# Ada_-_Base_Block_-_PSU_and_Connectors_Is.net
KiCad netlist of a schematic drawn in Altium Designer
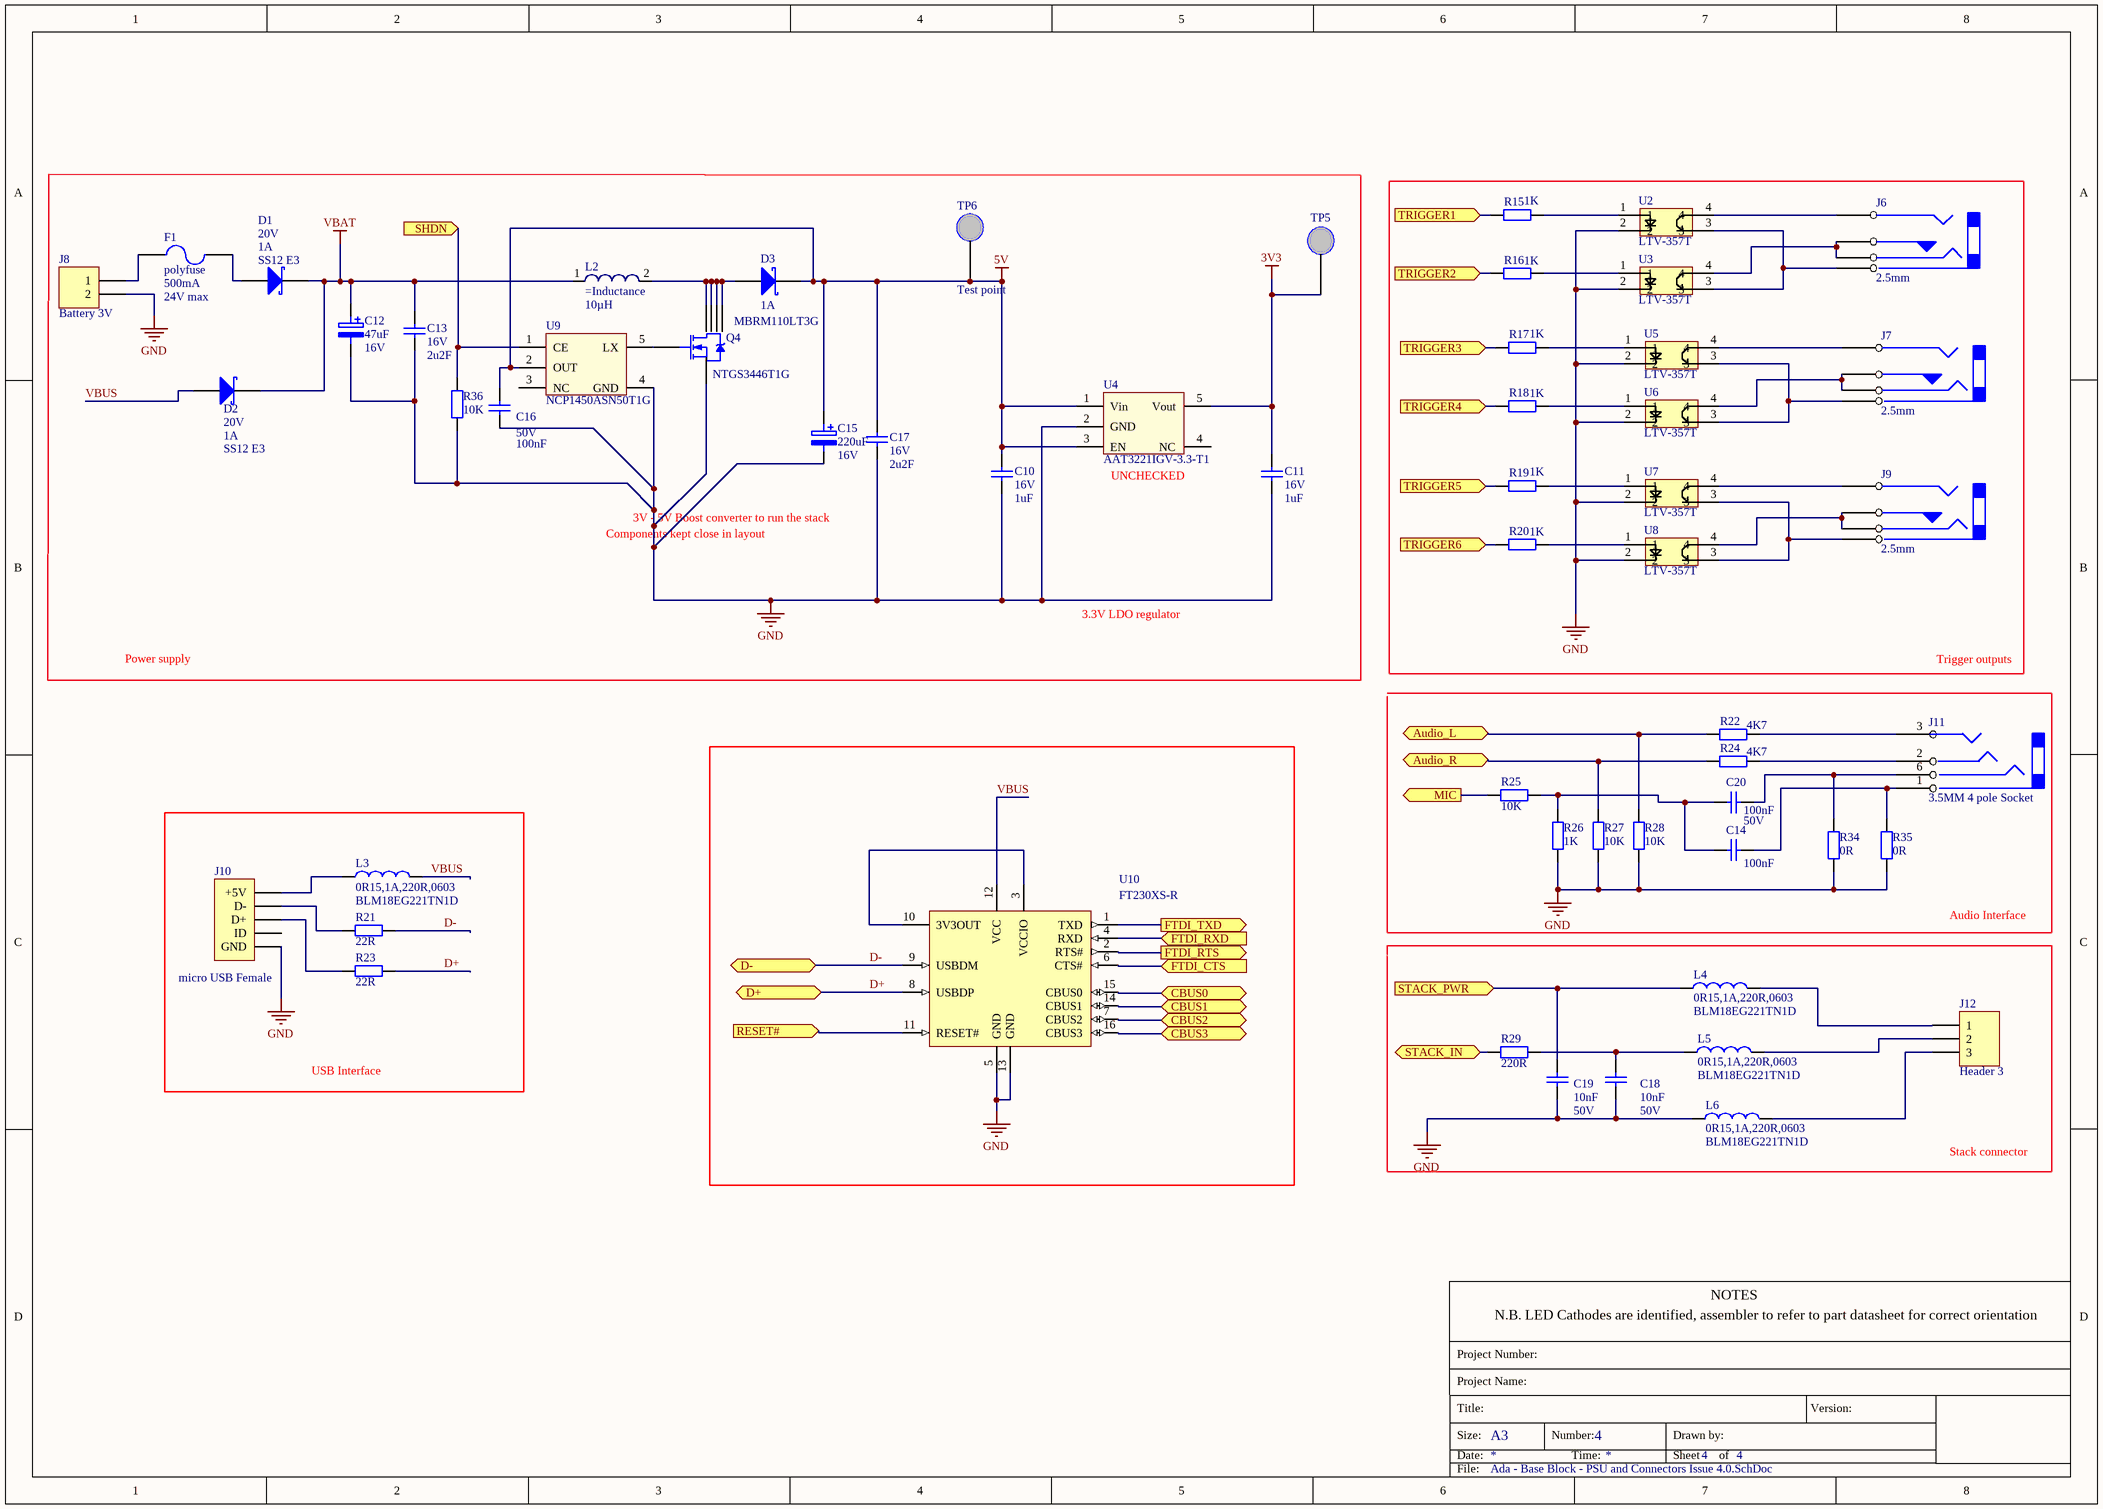
[diagram p0: Ada - Base Block - PSU and Connectors Issue 4.0.SchDoc]

(export (version "E")
  (design (tool "Eeschema 10.0.6"))
  (components
    (comp (ref "C10")
      (value "1uF")
      (footprint "C0603")
      (description "Ceramic")
      (fields
        (field (name "MANUFACTURER") "KEMET")
        (field (name "MANUF PART #") "C0603C105K4PAC")
        (field (name "VOLTAGE") "16V")
      )
      (libsource (lib "Capacitors") (part "1uF, 16V, 0603"))
    )
    (comp (ref "C11")
      (value "1uF")
      (footprint "C0603")
      (description "Ceramic")
      (fields
        (field (name "MANUFACTURER") "KEMET")
        (field (name "MANUF PART #") "C0603C105K4PAC")
        (field (name "VOLTAGE") "16V")
      )
      (libsource (lib "Capacitors") (part "1uF, 16V, 0603"))
    )
    (comp (ref "C12")
      (value "47uF")
      (footprint "CAP6.8/6.8")
      (description "Electrolitic")
      (fields
        (field (name "MANUFACTURER") "NICHICON")
        (field (name "MANUF PART #") "UUT1C470MCL1GS")
        (field (name "VOLTAGE") "16V")
      )
      (libsource (lib "Capacitors") (part "10uF, 16V, SMD"))
    )
    (comp (ref "C13")
      (value "2u2F")
      (footprint "C0603")
      (description "Ceramic")
      (fields
        (field (name "MANUFACTURER") "AVX")
        (field (name "MANUF PART #") "0603YD225KAT2A")
        (field (name "VOLTAGE") "16V")
      )
      (libsource (lib "Capacitors") (part "2u2F, 16V, 0603"))
    )
    (comp (ref "C14")
      (value "100nF")
      (footprint "C0603")
      (description "Ceramic")
      (fields (field (name "MANUFACTURER") "TruCap") (field (name "MANUF PART #") "U0603R103"))
      (libsource (lib "Capacitors") (part "100nF, 16V, 0603"))
    )
    (comp (ref "C15")
      (value "220uF")
      (footprint "CAP6.8/6.8")
      (description "Electrolitic")
      (fields
        (field (name "MANUFACTURER") "PANASONIC")
        (field (name "MANUF PART #") "EEEFPC221XAP")
        (field (name "VOLTAGE") "16V")
      )
      (libsource (lib "Capacitors") (part "220uF, 16V, SMD"))
    )
    (comp (ref "C16")
      (value "100nF")
      (footprint "C0603")
      (description "Ceramic")
      (fields
        (field (name "MANUFACTURER") "TruCap")
        (field (name "MANUF PART #") "U0603R103")
        (field (name "VOLTAGE") "50V")
      )
      (libsource (lib "Capacitors") (part "100nF, 16V, 0603"))
    )
    (comp (ref "C17")
      (value "2u2F")
      (footprint "C0603")
      (description "Ceramic")
      (fields
        (field (name "MANUFACTURER") "AVX")
        (field (name "MANUF PART #") "0603YD225KAT2A")
        (field (name "VOLTAGE") "16V")
      )
      (libsource (lib "Capacitors") (part "2u2F, 16V, 0603"))
    )
    (comp (ref "C18")
      (value "10nF")
      (footprint "C0603")
      (description "Ceramic")
      (fields
        (field (name "MANUFACTURER") "MULTICOMP")
        (field (name "MANUF PART #") "MCCA000238")
        (field (name "VOLTAGE") "50V")
      )
      (libsource (lib "Passives Rev B") (part "Capacitor 0603"))
    )
    (comp (ref "C19")
      (value "10nF")
      (footprint "C0603")
      (description "Ceramic")
      (fields
        (field (name "MANUFACTURER") "MULTICOMP")
        (field (name "MANUF PART #") "MCCA000238")
        (field (name "VOLTAGE") "50V")
      )
      (libsource (lib "Passives Rev B") (part "Capacitor 0603"))
    )
    (comp (ref "C20")
      (value "100nF")
      (footprint "C0603")
      (description "Ceramic")
      (fields
        (field (name "MANUFACTURER") "TruCap")
        (field (name "MANUF PART #") "U0603R103")
        (field (name "VOLTAGE") "50V")
      )
      (libsource (lib "Capacitors") (part "100nF, 16V, 0603"))
    )
    (comp (ref "D1")
      (value "SS12 E3")
      (footprint "DO214-AA")
      (description "SCHOTTKY DIODE")
      (fields
        (field (name "MANUFACTURER") "Taiwan Semiconductor")
        (field (name "PART NO.") "47-0988")
        (field (name "VOLTAGE") "20V")
        (field (name "CURRENT") "1A")
      )
      (libsource (lib "Diodes") (part "BYM13-40"))
    )
    (comp (ref "D2")
      (value "SS12 E3")
      (footprint "DO214-AA")
      (description "SCHOTTKY DIODE")
      (fields
        (field (name "MANUFACTURER") "Taiwan Semiconductor")
        (field (name "PART NO.") "47-0988")
        (field (name "VOLTAGE") "20V")
        (field (name "CURRENT") "1A")
      )
      (libsource (lib "Diodes") (part "BYM13-40"))
    )
    (comp (ref "D3")
      (value "MBRM110LT3G")
      (footprint "POWERMITE")
      (description "SCHOTTKY DIODE 1A, POWERMITE")
      (fields
        (field (name "MANUFACTURER") "ON SEMICONDUCTOR")
        (field (name "PART NO.") "1459062")
        (field (name "CURRENT") "1A")
      )
      (libsource (lib "Diodes") (part "MBRM110LT3G"))
    )
    (comp (ref "F1")
      (value "polyfuse")
      (footprint "1210 FUSE")
      (description "Polyfuse")
      (fields
        (field (name "MANUFACTURER") "LITTELFUSE")
        (field (name "MANUF PART #") "1210L050YR")
        (field (name "CURRENT") "500mA")
        (field (name "VOLTAGE") "24V max")
      )
      (libsource (lib "General") (part "500mA polyfuse"))
    )
    (comp (ref "J6")
      (value "2.5mm")
      (footprint "2.5mm socket TRI001")
      (description "2.5mm PHONEJACK STEREO")
      (fields (field (name "MANUFACTURER") "PRO SIGNAL") (field (name "MANUF PART #") "PSG01539"))
      (libsource (lib "Connectors") (part "2.5mm PHONEJACK STEREO TRI001"))
    )
    (comp (ref "J7")
      (value "2.5mm")
      (footprint "2.5mm socket TRI001")
      (description "2.5mm PHONEJACK STEREO")
      (fields (field (name "MANUFACTURER") "PRO SIGNAL") (field (name "MANUF PART #") "PSG01539"))
      (libsource (lib "Connectors") (part "2.5mm PHONEJACK STEREO TRI001"))
    )
    (comp (ref "J8")
      (value "Battery 3V")
      (footprint "Molex 0022057025")
      (description "Header, 2-Pin")
      (fields (field (name "MANUFACTURER") "MOLEX") (field (name "MANUF PART #") "22-05-7025"))
      (libsource (lib "Connectors") (part "Header 2"))
    )
    (comp (ref "J9")
      (value "2.5mm")
      (footprint "2.5mm socket TRI001")
      (description "2.5mm PHONEJACK STEREO")
      (fields (field (name "MANUFACTURER") "PRO SIGNAL") (field (name "MANUF PART #") "PSG01539"))
      (libsource (lib "Connectors") (part "2.5mm PHONEJACK STEREO TRI001"))
    )
    (comp (ref "J10")
      (value "micro USB Female")
      (footprint "micro usb receptacle")
      (description "Header, 5-Pin")
      (fields (field (name "MANUFACTURER") "FCI") (field (name "MANUF PART #") "10118192-0001LF"))
      (libsource (lib "Connectors") (part "micro USB Female"))
    )
    (comp (ref "J11")
      (value "3.5MM 4 pole Socket")
      (footprint "Cliff 3.5mm 4 pole socket")
      (description "3.5mm PHONEJACK STEREO")
      (fields (field (name "MANUFACTURER") "CLIFF ELECTRONIC") (field (name "MANUF PART #") "FC68125"))
      (libsource (lib "TRI002 Base Unit  Issue 1.1") (part "3.5mm PHONEJACK 4 pole"))
    )
    (comp (ref "J12")
      (value "Header 3")
      (footprint "sip3")
      (description "Header, 3-Pin")
      (libsource (lib "Connectors") (part "Header 3"))
    )
    (comp (ref "L2")
      (value "10µH")
      (footprint "WE-PD2_5848")
      (description "SMD Power Inductor WE-PD2, L=10.0 µH")
      (fields
        (field (name "MANUFACTURER") "Würth Elektronik eiSos GmbH")
        (field (name "MANUF PART #") "74477410")
      )
      (libsource (lib "Inductors") (part "WE-PD2 5848, M, 74477410"))
    )
    (comp (ref "L3")
      (value "0R15,1A,220R,0603")
      (footprint "L0603")
      (description "FERRITE BEAD")
      (fields
        (field (name "MANUFACTURER") "MURATA")
        (field (name "MANUF PART #") "BLM18EG221TN1D")
        (field (name "ALTIUM_VALUE") "BLM18EG221TN1D")
      )
      (libsource (lib "") (part "0R15,1A,220R,0603_1"))
    )
    (comp (ref "L4")
      (value "0R15,1A,220R,0603")
      (footprint "L0603")
      (description "FERRITE BEAD")
      (fields
        (field (name "MANUFACTURER") "MURATA")
        (field (name "MANUF PART #") "BLM18EG221TN1D")
        (field (name "ALTIUM_VALUE") "BLM18EG221TN1D")
      )
      (libsource (lib "Inductors") (part "0R15,1A,220R,0603"))
    )
    (comp (ref "L5")
      (value "0R15,1A,220R,0603")
      (footprint "L0603")
      (description "FERRITE BEAD")
      (fields
        (field (name "MANUFACTURER") "MURATA")
        (field (name "MANUF PART #") "BLM18EG221TN1D")
        (field (name "ALTIUM_VALUE") "BLM18EG221TN1D")
      )
      (libsource (lib "Inductors") (part "0R15,1A,220R,0603"))
    )
    (comp (ref "L6")
      (value "0R15,1A,220R,0603")
      (footprint "L0603")
      (description "FERRITE BEAD")
      (fields
        (field (name "MANUFACTURER") "MURATA")
        (field (name "MANUF PART #") "BLM18EG221TN1D")
        (field (name "ALTIUM_VALUE") "BLM18EG221TN1D")
      )
      (libsource (lib "Inductors") (part "0R15,1A,220R,0603"))
    )
    (comp (ref "Q4")
      (value "NTGS3446T1G")
      (footprint "TSOP6")
      (description "N-channel MOSFET Transistor 5.1A 20V, 6-Pin TSOP")
      (fields (field (name "MANUFACTURER") "ON Semiconductor") (field (name "PART NO.") "802-4221"))
      (libsource (lib "Transistors and FETs") (part "IRLML0060TRPBF"))
    )
    (comp (ref "R15")
      (value "1K")
      (footprint "R0603")
      (description "Resistor 0603")
      (libsource (lib "") (part "Resistor 0603_1"))
    )
    (comp (ref "R16")
      (value "1K")
      (footprint "R0603")
      (description "Resistor 0603")
      (libsource (lib "") (part "Resistor 0603_1"))
    )
    (comp (ref "R17")
      (value "1K")
      (footprint "R0603")
      (description "Resistor 0603")
      (libsource (lib "") (part "Resistor 0603_1"))
    )
    (comp (ref "R18")
      (value "1K")
      (footprint "R0603")
      (description "Resistor 0603")
      (libsource (lib "") (part "Resistor 0603_1"))
    )
    (comp (ref "R19")
      (value "1K")
      (footprint "R0603")
      (description "Resistor 0603")
      (libsource (lib "") (part "Resistor 0603_1"))
    )
    (comp (ref "R20")
      (value "1K")
      (footprint "R0603")
      (description "Resistor 0603")
      (libsource (lib "") (part "Resistor 0603_1"))
    )
    (comp (ref "R21")
      (value "22R")
      (footprint "R0603")
      (description "Resistor 0603")
      (libsource (lib "") (part "Resistor 0603_1"))
    )
    (comp (ref "R22")
      (value "4K7")
      (footprint "R0603")
      (description "Resistor 0603")
      (libsource (lib "") (part "Resistor 0603_1"))
    )
    (comp (ref "R23")
      (value "22R")
      (footprint "R0603")
      (description "Resistor 0603")
      (libsource (lib "") (part "Resistor 0603_1"))
    )
    (comp (ref "R24")
      (value "4K7")
      (footprint "R0603")
      (description "Resistor 0603")
      (libsource (lib "") (part "Resistor 0603_1"))
    )
    (comp (ref "R25")
      (value "10K")
      (footprint "R0603")
      (description "Resistor 0603")
      (libsource (lib "") (part "Resistor 0603_2"))
    )
    (comp (ref "R26")
      (value "1K")
      (footprint "R0603")
      (description "Resistor 0603")
      (libsource (lib "Passives Rev B") (part "Resistor 0603"))
    )
    (comp (ref "R27")
      (value "10K")
      (footprint "R0603")
      (description "Resistor 0603")
      (libsource (lib "Passives Rev B") (part "Resistor 0603"))
    )
    (comp (ref "R28")
      (value "10K")
      (footprint "R0603")
      (description "Resistor 0603")
      (libsource (lib "Passives Rev B") (part "Resistor 0603"))
    )
    (comp (ref "R29")
      (value "220R")
      (footprint "R0603")
      (description "Resistor 0603")
      (libsource (lib "") (part "Resistor 0603_2"))
    )
    (comp (ref "R34")
      (value "0R")
      (footprint "R0603")
      (description "Resistor 0603")
      (libsource (lib "Passives Rev B") (part "Resistor 0603"))
    )
    (comp (ref "R35")
      (value "0R")
      (footprint "R0603")
      (description "Resistor 0603")
      (libsource (lib "Passives Rev B") (part "Resistor 0603"))
    )
    (comp (ref "R36")
      (value "10K")
      (footprint "R0603")
      (description "Resistor 0603")
      (libsource (lib "Passives Rev B") (part "Resistor 0603"))
    )
    (comp (ref "TP5")
      (value "Test point")
      (footprint "TP")
      (description "Test Point")
      (libsource (lib "General") (part "Test point"))
    )
    (comp (ref "TP6")
      (value "Test point")
      (footprint "TP")
      (description "Test Point")
      (libsource (lib "General") (part "Test point"))
    )
    (comp (ref "U2")
      (value "LTV-357T")
      (footprint "SMD-4")
      (description "OPTOCOUPLER, 5KV, TRANSISTOR O/P")
      (fields (field (name "MANUFACTURER") "Lite-on") (field (name "PART NO.") "859-LTV-357T"))
      (libsource (lib "TRI002 Base Unit  Issue 1.3") (part "LTV-817"))
    )
    (comp (ref "U3")
      (value "LTV-357T")
      (footprint "SMD-4")
      (description "OPTOCOUPLER, 5KV, TRANSISTOR O/P")
      (fields (field (name "MANUFACTURER") "Lite-on") (field (name "PART NO.") "859-LTV-357T"))
      (libsource (lib "TRI002 Base Unit  Issue 1.3") (part "LTV-817"))
    )
    (comp (ref "U4")
      (value "AAT3221IGV-3.3-T1")
      (footprint "TSOT 5 pin")
      (description "3.3V LDO Regulator")
      (fields
        (field (name "MANUFACTURER") "Skyworks Solutions")
        (field (name "PART NO.") "873-AAT3221IGV-33T1")
      )
      (libsource (lib "TRI002 Base Unit  Issue 1.3") (part "AAT3221IGV-3.3-T1"))
    )
    (comp (ref "U5")
      (value "LTV-357T")
      (footprint "SMD-4")
      (description "OPTOCOUPLER, 5KV, TRANSISTOR O/P")
      (fields (field (name "MANUFACTURER") "Lite-on") (field (name "PART NO.") "859-LTV-357T"))
      (libsource (lib "TRI002 Base Unit  Issue 1.3") (part "LTV-817"))
    )
    (comp (ref "U6")
      (value "LTV-357T")
      (footprint "SMD-4")
      (description "OPTOCOUPLER, 5KV, TRANSISTOR O/P")
      (fields (field (name "MANUFACTURER") "Lite-on") (field (name "PART NO.") "859-LTV-357T"))
      (libsource (lib "TRI002 Base Unit  Issue 1.3") (part "LTV-817"))
    )
    (comp (ref "U7")
      (value "LTV-357T")
      (footprint "SMD-4")
      (description "OPTOCOUPLER, 5KV, TRANSISTOR O/P")
      (fields (field (name "MANUFACTURER") "Lite-on") (field (name "PART NO.") "859-LTV-357T"))
      (libsource (lib "TRI002 Base Unit  Issue 1.3") (part "LTV-817"))
    )
    (comp (ref "U8")
      (value "LTV-357T")
      (footprint "SMD-4")
      (description "OPTOCOUPLER, 5KV, TRANSISTOR O/P")
      (fields (field (name "MANUFACTURER") "Lite-on") (field (name "PART NO.") "859-LTV-357T"))
      (libsource (lib "TRI002 Base Unit  Issue 1.3") (part "LTV-817"))
    )
    (comp (ref "U9")
      (value "NCP1450ASN50T1G")
      (footprint "SOT23-5AN")
      (description "DC-DC STEP UP CONVERTER, 5.0V, SMD")
      (fields (field (name "MANUFACTURER") "ON SEMICONDUCTOR") (field (name "PART NO.") "1460676"))
      (libsource (lib "TRI002_SCHLIB_1.3") (part "NCP1402SN50T1G"))
    )
    (comp (ref "U10")
      (value "FT230XS-R")
      (footprint "SSOP-16_N")
      (fields (field (name "MANUFACTURER") "FTDI") (field (name "PART NO.") "895-FT230XS-R"))
      (libsource (lib "FTDI FT-X Series") (part "FT230XS-R"))
    )
  )
  (nets
    (net (code "1") (name "/Audio_L") (class "Default")
      (node (ref "R22") (pin "2") (pinfunction "2_2") (pintype "passive"))
      (node (ref "R28") (pin "1") (pinfunction "1_1") (pintype "passive"))
    )
    (net (code "2") (name "/Audio_R") (class "Default")
      (node (ref "R24") (pin "2") (pinfunction "2_2") (pintype "passive"))
      (node (ref "R27") (pin "1") (pinfunction "1_1") (pintype "passive"))
    )
    (net (code "3") (name "/CBUS0") (class "Default")
      (node (ref "U10") (pin "15") (pinfunction "CBUS0_15") (pintype "bidirectional"))
    )
    (net (code "4") (name "/CBUS1") (class "Default")
      (node (ref "U10") (pin "14") (pinfunction "CBUS1_14") (pintype "bidirectional"))
    )
    (net (code "5") (name "/CBUS2") (class "Default")
      (node (ref "U10") (pin "7") (pinfunction "CBUS2_7") (pintype "bidirectional"))
    )
    (net (code "6") (name "/CBUS3") (class "Default")
      (node (ref "U10") (pin "16") (pinfunction "CBUS3_16") (pintype "bidirectional"))
    )
    (net (code "7") (name "/D+") (class "Default")
      (node (ref "R23") (pin "1") (pinfunction "1_1") (pintype "passive"))
      (node (ref "U10") (pin "8") (pinfunction "USBDP_8") (pintype "input"))
    )
    (net (code "8") (name "/D-") (class "Default")
      (node (ref "R21") (pin "1") (pinfunction "1_1") (pintype "passive"))
      (node (ref "U10") (pin "9") (pinfunction "USBDM_9") (pintype "input"))
    )
    (net (code "9") (name "/FTDI_CTS") (class "Default")
      (node (ref "U10") (pin "6") (pinfunction "CTS#_6") (pintype "input"))
    )
    (net (code "10") (name "/FTDI_RTS") (class "Default")
      (node (ref "U10") (pin "2") (pinfunction "RTS#_2") (pintype "output"))
    )
    (net (code "11") (name "/FTDI_RXD") (class "Default")
      (node (ref "U10") (pin "4") (pinfunction "RXD_4") (pintype "input"))
    )
    (net (code "12") (name "/FTDI_TXD") (class "Default")
      (node (ref "U10") (pin "1") (pinfunction "TXD_1") (pintype "output"))
    )
    (net (code "13") (name "/MIC") (class "Default")
      (node (ref "R25") (pin "1") (pinfunction "1_1") (pintype "passive"))
    )
    (net (code "14") (name "/RESET#") (class "Default")
      (node (ref "U10") (pin "11") (pinfunction "RESET#_11") (pintype "input"))
    )
    (net (code "15") (name "/SHDN") (class "Default")
      (node (ref "R36") (pin "1") (pinfunction "1_1") (pintype "passive"))
      (node (ref "U9") (pin "1") (pinfunction "CE_1") (pintype "passive"))
    )
    (net (code "16") (name "/STACK_IN") (class "Default")
      (node (ref "R29") (pin "1") (pinfunction "1_1") (pintype "passive"))
    )
    (net (code "17") (name "/STACK_PWR") (class "Default")
      (node (ref "C19") (pin "2") (pinfunction "2_2") (pintype "passive"))
      (node (ref "L4") (pin "2") (pinfunction "2_2") (pintype "passive"))
    )
    (net (code "18") (name "/TRIGGER1") (class "Default")
      (node (ref "R15") (pin "2") (pinfunction "2_2") (pintype "passive"))
    )
    (net (code "19") (name "/TRIGGER2") (class "Default")
      (node (ref "R16") (pin "2") (pinfunction "2_2") (pintype "passive"))
    )
    (net (code "20") (name "/TRIGGER3") (class "Default")
      (node (ref "R17") (pin "2") (pinfunction "2_2") (pintype "passive"))
    )
    (net (code "21") (name "/TRIGGER4") (class "Default")
      (node (ref "R18") (pin "2") (pinfunction "2_2") (pintype "passive"))
    )
    (net (code "22") (name "/TRIGGER5") (class "Default")
      (node (ref "R19") (pin "2") (pinfunction "2_2") (pintype "passive"))
    )
    (net (code "23") (name "/TRIGGER6") (class "Default")
      (node (ref "R20") (pin "2") (pinfunction "2_2") (pintype "passive"))
    )
    (net (code "24") (name "/VBUS") (class "Default")
      (node (ref "D2") (pin "A") (pinfunction "A_A") (pintype "passive"))
      (node (ref "L3") (pin "2") (pinfunction "2_2") (pintype "passive"))
      (node (ref "U10") (pin "12") (pinfunction "VCC_12") (pintype "power_in"))
    )
    (net (code "25") (name "3V3") (class "Default")
      (node (ref "C11") (pin "2") (pinfunction "2_2") (pintype "passive"))
      (node (ref "TP5") (pin "1") (pinfunction "1_1") (pintype "passive"))
      (node (ref "U4") (pin "5") (pinfunction "Vout_5") (pintype "passive"))
    )
    (net (code "26") (name "5V") (class "Default")
      (node (ref "C10") (pin "2") (pinfunction "2_2") (pintype "passive"))
      (node (ref "C15") (pin "1") (pinfunction "1_1") (pintype "passive"))
      (node (ref "C16") (pin "2") (pinfunction "2_2") (pintype "passive"))
      (node (ref "C17") (pin "2") (pinfunction "2_2") (pintype "passive"))
      (node (ref "D3") (pin "K") (pinfunction "K_K") (pintype "passive"))
      (node (ref "TP6") (pin "1") (pinfunction "1_1") (pintype "passive"))
      (node (ref "U4") (pin "1") (pinfunction "Vin_1") (pintype "passive"))
      (node (ref "U4") (pin "3") (pinfunction "EN_3") (pintype "passive"))
      (node (ref "U9") (pin "2") (pinfunction "OUT_2") (pintype "passive"))
    )
    (net (code "27") (name "GND") (class "Default")
      (node (ref "C10") (pin "1") (pinfunction "1_1") (pintype "passive"))
      (node (ref "C11") (pin "1") (pinfunction "1_1") (pintype "passive"))
      (node (ref "C12") (pin "2") (pinfunction "2_2") (pintype "passive"))
      (node (ref "C13") (pin "1") (pinfunction "1_1") (pintype "passive"))
      (node (ref "C15") (pin "2") (pinfunction "2_2") (pintype "passive"))
      (node (ref "C16") (pin "1") (pinfunction "1_1") (pintype "passive"))
      (node (ref "C17") (pin "1") (pinfunction "1_1") (pintype "passive"))
      (node (ref "C18") (pin "1") (pinfunction "1_1") (pintype "passive"))
      (node (ref "C19") (pin "1") (pinfunction "1_1") (pintype "passive"))
      (node (ref "J10") (pin "5") (pinfunction "GND_5") (pintype "passive"))
      (node (ref "J8") (pin "2") (pinfunction "2_2") (pintype "passive"))
      (node (ref "L6") (pin "2") (pinfunction "2_2") (pintype "passive"))
      (node (ref "Q4") (pin "4") (pinfunction "S_4") (pintype "passive"))
      (node (ref "R26") (pin "2") (pinfunction "2_2") (pintype "passive"))
      (node (ref "R27") (pin "2") (pinfunction "2_2") (pintype "passive"))
      (node (ref "R28") (pin "2") (pinfunction "2_2") (pintype "passive"))
      (node (ref "R34") (pin "2") (pinfunction "2_2") (pintype "passive"))
      (node (ref "R35") (pin "2") (pinfunction "2_2") (pintype "passive"))
      (node (ref "R36") (pin "2") (pinfunction "2_2") (pintype "passive"))
      (node (ref "U10") (pin "13") (pinfunction "GND_13") (pintype "power_in"))
      (node (ref "U10") (pin "5") (pinfunction "GND_5") (pintype "power_in"))
      (node (ref "U2") (pin "2") (pinfunction "2_2") (pintype "passive"))
      (node (ref "U3") (pin "2") (pinfunction "2_2") (pintype "passive"))
      (node (ref "U4") (pin "2") (pinfunction "GND_2") (pintype "passive"))
      (node (ref "U5") (pin "2") (pinfunction "2_2") (pintype "passive"))
      (node (ref "U6") (pin "2") (pinfunction "2_2") (pintype "passive"))
      (node (ref "U7") (pin "2") (pinfunction "2_2") (pintype "passive"))
      (node (ref "U8") (pin "2") (pinfunction "2_2") (pintype "passive"))
      (node (ref "U9") (pin "4") (pinfunction "GND_4") (pintype "passive"))
    )
    (net (code "28") (name "Net-(C14-Pad1)") (class "Default")
      (node (ref "C14") (pin "1") (pinfunction "1_1") (pintype "passive"))
      (node (ref "J11") (pin "1") (pinfunction "1_1") (pintype "passive"))
      (node (ref "R35") (pin "1") (pinfunction "1_1") (pintype "passive"))
    )
    (net (code "29") (name "Net-(C14-Pad2)") (class "Default")
      (node (ref "C14") (pin "2") (pinfunction "2_2") (pintype "passive"))
      (node (ref "C20") (pin "2") (pinfunction "2_2") (pintype "passive"))
      (node (ref "R25") (pin "2") (pinfunction "2_2") (pintype "passive"))
      (node (ref "R26") (pin "1") (pinfunction "1_1") (pintype "passive"))
    )
    (net (code "30") (name "Net-(C18-Pad2)") (class "Default")
      (node (ref "C18") (pin "2") (pinfunction "2_2") (pintype "passive"))
      (node (ref "L5") (pin "2") (pinfunction "2_2") (pintype "passive"))
      (node (ref "R29") (pin "2") (pinfunction "2_2") (pintype "passive"))
    )
    (net (code "31") (name "Net-(C20-Pad1)") (class "Default")
      (node (ref "C20") (pin "1") (pinfunction "1_1") (pintype "passive"))
      (node (ref "J11") (pin "6") (pinfunction "6_6") (pintype "passive"))
      (node (ref "R34") (pin "1") (pinfunction "1_1") (pintype "passive"))
    )
    (net (code "32") (name "Net-(D1-PadA)") (class "Default")
      (node (ref "D1") (pin "A") (pinfunction "A_A") (pintype "passive"))
      (node (ref "F1") (pin "2") (pinfunction "2_2") (pintype "passive"))
    )
    (net (code "33") (name "Net-(D3-PadA)") (class "Default")
      (node (ref "D3") (pin "A") (pinfunction "A_A") (pintype "passive"))
      (node (ref "L2") (pin "2") (pinfunction "2_2") (pintype "passive"))
      (node (ref "Q4") (pin "1") (pinfunction "D_1") (pintype "passive"))
      (node (ref "Q4") (pin "2") (pinfunction "D_2") (pintype "passive"))
      (node (ref "Q4") (pin "5") (pinfunction "D_5") (pintype "passive"))
      (node (ref "Q4") (pin "6") (pinfunction "D_6") (pintype "passive"))
    )
    (net (code "34") (name "Net-(F1-Pad1)") (class "Default")
      (node (ref "F1") (pin "1") (pinfunction "1_1") (pintype "passive"))
      (node (ref "J8") (pin "1") (pinfunction "1_1") (pintype "passive"))
    )
    (net (code "35") (name "Net-(J6-Pad1)") (class "Default")
      (node (ref "J6") (pin "1") (pinfunction "1_1") (pintype "passive"))
      (node (ref "U2") (pin "3") (pinfunction "3_3") (pintype "passive"))
      (node (ref "U3") (pin "3") (pinfunction "3_3") (pintype "passive"))
    )
    (net (code "36") (name "Net-(J6-Pad2)") (class "Default")
      (node (ref "J6") (pin "2") (pinfunction "2_2") (pintype "passive"))
      (node (ref "J6") (pin "3") (pinfunction "3_3") (pintype "passive"))
      (node (ref "U3") (pin "4") (pinfunction "4_4") (pintype "passive"))
    )
    (net (code "37") (name "Net-(J6-Pad4)") (class "Default")
      (node (ref "J6") (pin "4") (pinfunction "4_4") (pintype "passive"))
      (node (ref "U2") (pin "4") (pinfunction "4_4") (pintype "passive"))
    )
    (net (code "38") (name "Net-(J7-Pad1)") (class "Default")
      (node (ref "J7") (pin "1") (pinfunction "1_1") (pintype "passive"))
      (node (ref "U5") (pin "3") (pinfunction "3_3") (pintype "passive"))
      (node (ref "U6") (pin "3") (pinfunction "3_3") (pintype "passive"))
    )
    (net (code "39") (name "Net-(J7-Pad2)") (class "Default")
      (node (ref "J7") (pin "2") (pinfunction "2_2") (pintype "passive"))
      (node (ref "J7") (pin "3") (pinfunction "3_3") (pintype "passive"))
      (node (ref "U6") (pin "4") (pinfunction "4_4") (pintype "passive"))
    )
    (net (code "40") (name "Net-(J7-Pad4)") (class "Default")
      (node (ref "J7") (pin "4") (pinfunction "4_4") (pintype "passive"))
      (node (ref "U5") (pin "4") (pinfunction "4_4") (pintype "passive"))
    )
    (net (code "41") (name "Net-(J9-Pad1)") (class "Default")
      (node (ref "J9") (pin "1") (pinfunction "1_1") (pintype "passive"))
      (node (ref "U7") (pin "3") (pinfunction "3_3") (pintype "passive"))
      (node (ref "U8") (pin "3") (pinfunction "3_3") (pintype "passive"))
    )
    (net (code "42") (name "Net-(J9-Pad2)") (class "Default")
      (node (ref "J9") (pin "2") (pinfunction "2_2") (pintype "passive"))
      (node (ref "J9") (pin "3") (pinfunction "3_3") (pintype "passive"))
      (node (ref "U8") (pin "4") (pinfunction "4_4") (pintype "passive"))
    )
    (net (code "43") (name "Net-(J9-Pad4)") (class "Default")
      (node (ref "J9") (pin "4") (pinfunction "4_4") (pintype "passive"))
      (node (ref "U7") (pin "4") (pinfunction "4_4") (pintype "passive"))
    )
    (net (code "44") (name "Net-(J10-+5V)") (class "Default")
      (node (ref "J10") (pin "1") (pinfunction "+5V_1") (pintype "passive"))
      (node (ref "L3") (pin "1") (pinfunction "1_1") (pintype "passive"))
    )
    (net (code "45") (name "Net-(J10-D+)") (class "Default")
      (node (ref "J10") (pin "3") (pinfunction "D+_3") (pintype "passive"))
      (node (ref "R23") (pin "2") (pinfunction "2_2") (pintype "passive"))
    )
    (net (code "46") (name "Net-(J10-D-)") (class "Default")
      (node (ref "J10") (pin "2") (pinfunction "D-_2") (pintype "passive"))
      (node (ref "R21") (pin "2") (pinfunction "2_2") (pintype "passive"))
    )
    (net (code "47") (name "Net-(J11-Pad2)") (class "Default")
      (node (ref "J11") (pin "2") (pinfunction "2_2") (pintype "passive"))
      (node (ref "R24") (pin "1") (pinfunction "1_1") (pintype "passive"))
    )
    (net (code "48") (name "Net-(J11-Pad3)") (class "Default")
      (node (ref "J11") (pin "3") (pinfunction "3_3") (pintype "passive"))
      (node (ref "R22") (pin "1") (pinfunction "1_1") (pintype "passive"))
    )
    (net (code "49") (name "Net-(J12-Pad1)") (class "Default")
      (node (ref "J12") (pin "1") (pinfunction "1_1") (pintype "passive"))
      (node (ref "L4") (pin "1") (pinfunction "1_1") (pintype "passive"))
    )
    (net (code "50") (name "Net-(J12-Pad2)") (class "Default")
      (node (ref "J12") (pin "2") (pinfunction "2_2") (pintype "passive"))
      (node (ref "L5") (pin "1") (pinfunction "1_1") (pintype "passive"))
    )
    (net (code "51") (name "Net-(J12-Pad3)") (class "Default")
      (node (ref "J12") (pin "3") (pinfunction "3_3") (pintype "passive"))
      (node (ref "L6") (pin "1") (pinfunction "1_1") (pintype "passive"))
    )
    (net (code "52") (name "Net-(Q4-G)") (class "Default")
      (node (ref "Q4") (pin "3") (pinfunction "G_3") (pintype "passive"))
      (node (ref "U9") (pin "5") (pinfunction "LX_5") (pintype "passive"))
    )
    (net (code "53") (name "Net-(R15-Pad1)") (class "Default")
      (node (ref "R15") (pin "1") (pinfunction "1_1") (pintype "passive"))
      (node (ref "U2") (pin "1") (pinfunction "1_1") (pintype "passive"))
    )
    (net (code "54") (name "Net-(R16-Pad1)") (class "Default")
      (node (ref "R16") (pin "1") (pinfunction "1_1") (pintype "passive"))
      (node (ref "U3") (pin "1") (pinfunction "1_1") (pintype "passive"))
    )
    (net (code "55") (name "Net-(R17-Pad1)") (class "Default")
      (node (ref "R17") (pin "1") (pinfunction "1_1") (pintype "passive"))
      (node (ref "U5") (pin "1") (pinfunction "1_1") (pintype "passive"))
    )
    (net (code "56") (name "Net-(R18-Pad1)") (class "Default")
      (node (ref "R18") (pin "1") (pinfunction "1_1") (pintype "passive"))
      (node (ref "U6") (pin "1") (pinfunction "1_1") (pintype "passive"))
    )
    (net (code "57") (name "Net-(R19-Pad1)") (class "Default")
      (node (ref "R19") (pin "1") (pinfunction "1_1") (pintype "passive"))
      (node (ref "U7") (pin "1") (pinfunction "1_1") (pintype "passive"))
    )
    (net (code "58") (name "Net-(R20-Pad1)") (class "Default")
      (node (ref "R20") (pin "1") (pinfunction "1_1") (pintype "passive"))
      (node (ref "U8") (pin "1") (pinfunction "1_1") (pintype "passive"))
    )
    (net (code "59") (name "Net-(U10-3V3OUT)") (class "Default")
      (node (ref "U10") (pin "10") (pinfunction "3V3OUT_10") (pintype "power_in"))
      (node (ref "U10") (pin "3") (pinfunction "VCCIO_3") (pintype "power_in"))
    )
    (net (code "60") (name "VBAT") (class "Default")
      (node (ref "C12") (pin "1") (pinfunction "1_1") (pintype "passive"))
      (node (ref "C13") (pin "2") (pinfunction "2_2") (pintype "passive"))
      (node (ref "D1") (pin "K") (pinfunction "K_K") (pintype "passive"))
      (node (ref "D2") (pin "K") (pinfunction "K_K") (pintype "passive"))
      (node (ref "L2") (pin "1") (pinfunction "1_1") (pintype "passive"))
    )
    (net (code "61") (name "unconnected-(J10-ID-Pad4)") (class "Default")
      (node (ref "J10") (pin "4") (pinfunction "ID_4") (pintype "passive"))
    )
    (net (code "62") (name "unconnected-(U4-NC-Pad4)") (class "Default")
      (node (ref "U4") (pin "4") (pinfunction "NC_4") (pintype "passive"))
    )
    (net (code "63") (name "unconnected-(U9-NC-Pad3)") (class "Default")
      (node (ref "U9") (pin "3") (pinfunction "NC_3") (pintype "passive"))
    )
  )
)
